# LO.net
KiCad netlist of a schematic drawn in Altium Designer
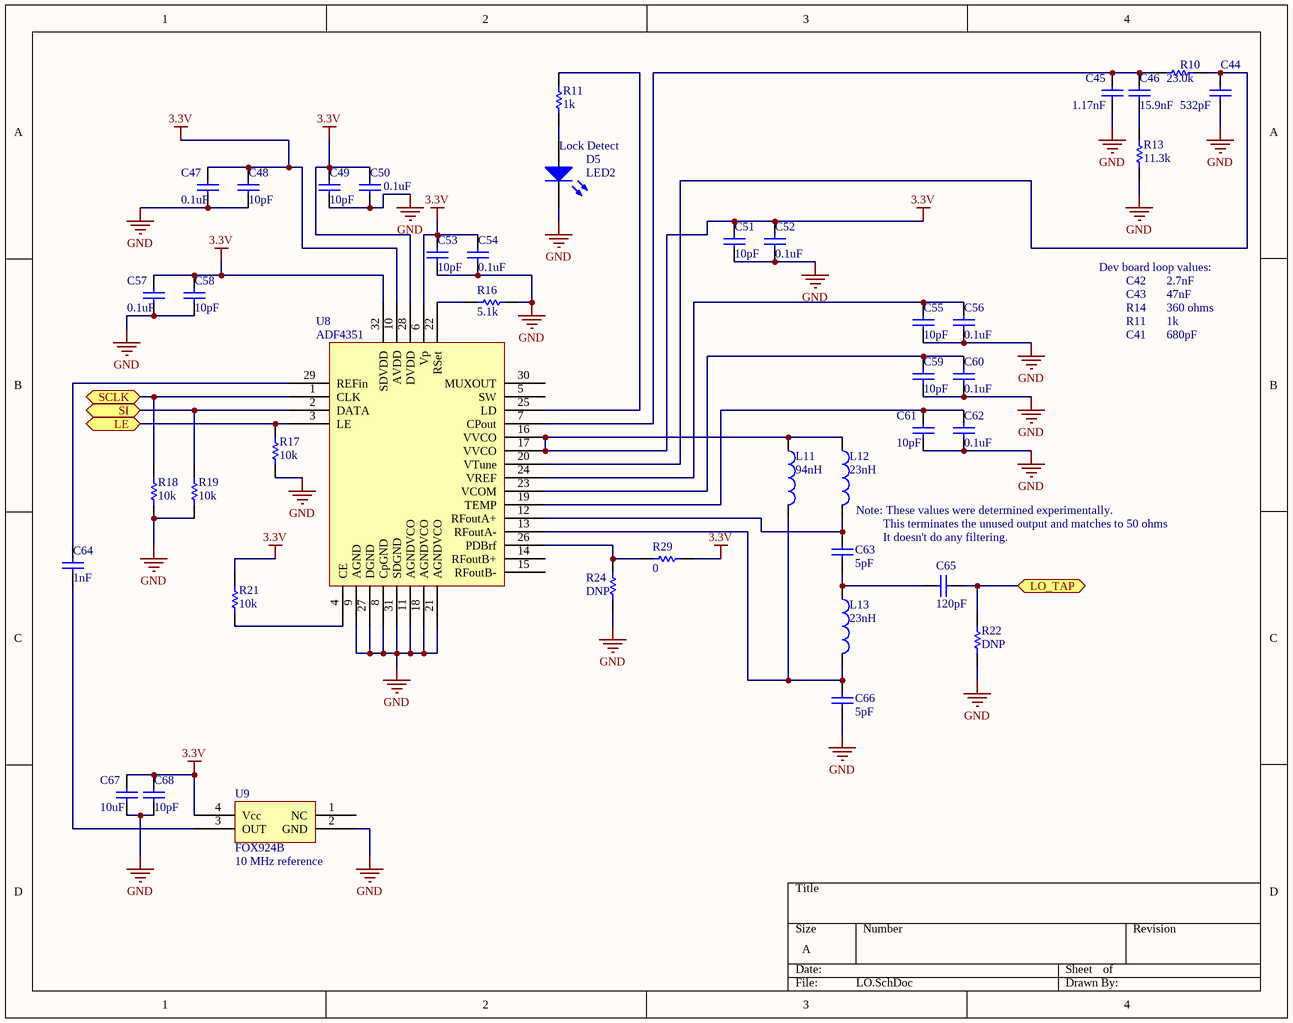
[diagram p0: LO.SchDoc]

(export (version "E")
  (design (tool "Eeschema 10.0.6"))
  (components
    (comp (ref "C44")
      (value "532pF")
      (footprint "0402")
      (description "Capacitor (Semiconductor SIM Model)")
      (fields (field (name "Comment") "Cap Semi") (field (name "PUBLISHER") "Altium Limited"))
      (libsource (lib "Miscellaneous Devices") (part "Cap Semi"))
    )
    (comp (ref "C45")
      (value "1.17nF")
      (footprint "0402")
      (description "Capacitor (Semiconductor SIM Model)")
      (fields (field (name "Comment") "Cap Semi") (field (name "PUBLISHER") "Altium Limited"))
      (libsource (lib "Miscellaneous Devices") (part "Cap Semi"))
    )
    (comp (ref "C46")
      (value "15.9nF")
      (footprint "0402")
      (description "Capacitor (Semiconductor SIM Model)")
      (fields (field (name "Comment") "Cap Semi") (field (name "PUBLISHER") "Altium Limited"))
      (libsource (lib "Miscellaneous Devices") (part "Cap Semi"))
    )
    (comp (ref "C47")
      (value "0.1uF")
      (footprint "0402")
      (description "Capacitor (Semiconductor SIM Model)")
      (fields (field (name "Comment") "Cap Semi") (field (name "PUBLISHER") "Altium Limited"))
      (libsource (lib "Miscellaneous Devices") (part "Cap Semi"))
    )
    (comp (ref "C48")
      (value "10pF")
      (footprint "0402")
      (description "Capacitor (Semiconductor SIM Model)")
      (fields (field (name "Comment") "Cap Semi") (field (name "PUBLISHER") "Altium Limited"))
      (libsource (lib "Miscellaneous Devices") (part "Cap Semi"))
    )
    (comp (ref "C49")
      (value "10pF")
      (footprint "0402")
      (description "Capacitor (Semiconductor SIM Model)")
      (fields (field (name "Comment") "Cap Semi") (field (name "PUBLISHER") "Altium Limited"))
      (libsource (lib "Miscellaneous Devices") (part "Cap Semi"))
    )
    (comp (ref "C50")
      (value "0.1uF")
      (footprint "0402")
      (description "Capacitor (Semiconductor SIM Model)")
      (fields (field (name "Comment") "Cap Semi") (field (name "PUBLISHER") "Altium Limited"))
      (libsource (lib "Miscellaneous Devices") (part "Cap Semi"))
    )
    (comp (ref "C51")
      (value "10pF")
      (footprint "0402")
      (description "Capacitor (Semiconductor SIM Model)")
      (fields (field (name "Comment") "Cap Semi") (field (name "PUBLISHER") "Altium Limited"))
      (libsource (lib "Miscellaneous Devices") (part "Cap Semi"))
    )
    (comp (ref "C52")
      (value "0.1uF")
      (footprint "0402")
      (description "Capacitor (Semiconductor SIM Model)")
      (fields (field (name "Comment") "Cap Semi") (field (name "PUBLISHER") "Altium Limited"))
      (libsource (lib "Miscellaneous Devices") (part "Cap Semi"))
    )
    (comp (ref "C53")
      (value "10pF")
      (footprint "0402")
      (description "Capacitor (Semiconductor SIM Model)")
      (fields (field (name "Comment") "Cap Semi") (field (name "PUBLISHER") "Altium Limited"))
      (libsource (lib "Miscellaneous Devices") (part "Cap Semi"))
    )
    (comp (ref "C54")
      (value "0.1uF")
      (footprint "0402")
      (description "Capacitor (Semiconductor SIM Model)")
      (fields (field (name "Comment") "Cap Semi") (field (name "PUBLISHER") "Altium Limited"))
      (libsource (lib "Miscellaneous Devices") (part "Cap Semi"))
    )
    (comp (ref "C55")
      (value "10pF")
      (footprint "0402")
      (description "Capacitor (Semiconductor SIM Model)")
      (fields (field (name "Comment") "Cap Semi") (field (name "PUBLISHER") "Altium Limited"))
      (libsource (lib "Miscellaneous Devices") (part "Cap Semi"))
    )
    (comp (ref "C56")
      (value "0.1uF")
      (footprint "0402")
      (description "Capacitor (Semiconductor SIM Model)")
      (fields (field (name "Comment") "Cap Semi") (field (name "PUBLISHER") "Altium Limited"))
      (libsource (lib "Miscellaneous Devices") (part "Cap Semi"))
    )
    (comp (ref "C57")
      (value "0.1uF")
      (footprint "0402")
      (description "Capacitor (Semiconductor SIM Model)")
      (fields (field (name "Comment") "Cap Semi") (field (name "PUBLISHER") "Altium Limited"))
      (libsource (lib "Miscellaneous Devices") (part "Cap Semi"))
    )
    (comp (ref "C58")
      (value "10pF")
      (footprint "0402")
      (description "Capacitor (Semiconductor SIM Model)")
      (fields (field (name "Comment") "Cap Semi") (field (name "PUBLISHER") "Altium Limited"))
      (libsource (lib "Miscellaneous Devices") (part "Cap Semi"))
    )
    (comp (ref "C59")
      (value "10pF")
      (footprint "0402")
      (description "Capacitor (Semiconductor SIM Model)")
      (fields (field (name "Comment") "Cap Semi") (field (name "PUBLISHER") "Altium Limited"))
      (libsource (lib "Miscellaneous Devices") (part "Cap Semi"))
    )
    (comp (ref "C60")
      (value "0.1uF")
      (footprint "0402")
      (description "Capacitor (Semiconductor SIM Model)")
      (fields (field (name "Comment") "Cap Semi") (field (name "PUBLISHER") "Altium Limited"))
      (libsource (lib "Miscellaneous Devices") (part "Cap Semi"))
    )
    (comp (ref "C61")
      (value "10pF")
      (footprint "0402")
      (description "Capacitor (Semiconductor SIM Model)")
      (fields (field (name "Comment") "Cap Semi") (field (name "PUBLISHER") "Altium Limited"))
      (libsource (lib "Miscellaneous Devices") (part "Cap Semi"))
    )
    (comp (ref "C62")
      (value "0.1uF")
      (footprint "0402")
      (description "Capacitor (Semiconductor SIM Model)")
      (fields (field (name "Comment") "Cap Semi") (field (name "PUBLISHER") "Altium Limited"))
      (libsource (lib "Miscellaneous Devices") (part "Cap Semi"))
    )
    (comp (ref "C63")
      (value "5pF")
      (footprint "0402")
      (description "Capacitor (Semiconductor SIM Model)")
      (fields (field (name "Comment") "Cap Semi") (field (name "PUBLISHER") "Altium Limited"))
      (libsource (lib "Miscellaneous Devices") (part "Cap Semi"))
    )
    (comp (ref "C64")
      (value "1nF")
      (footprint "0402")
      (description "Capacitor (Semiconductor SIM Model)")
      (fields (field (name "Comment") "Cap Semi") (field (name "PUBLISHER") "Altium Limited"))
      (libsource (lib "Miscellaneous Devices") (part "Cap Semi"))
    )
    (comp (ref "C65")
      (value "120pF")
      (footprint "0402")
      (description "Capacitor (Semiconductor SIM Model)")
      (fields (field (name "Comment") "Cap Semi") (field (name "PUBLISHER") "Altium Limited"))
      (libsource (lib "Miscellaneous Devices") (part "Cap Semi"))
    )
    (comp (ref "C66")
      (value "5pF")
      (footprint "0402")
      (description "Capacitor (Semiconductor SIM Model)")
      (fields (field (name "Comment") "Cap Semi") (field (name "PUBLISHER") "Altium Limited"))
      (libsource (lib "Miscellaneous Devices") (part "Cap Semi"))
    )
    (comp (ref "C67")
      (value "10uF")
      (footprint "0402")
      (description "Capacitor (Semiconductor SIM Model)")
      (fields (field (name "Comment") "Cap Semi") (field (name "PUBLISHER") "Altium Limited"))
      (libsource (lib "Miscellaneous Devices") (part "Cap Semi"))
    )
    (comp (ref "C68")
      (value "10pF")
      (footprint "0402")
      (description "Capacitor (Semiconductor SIM Model)")
      (fields (field (name "Comment") "Cap Semi") (field (name "PUBLISHER") "Altium Limited"))
      (libsource (lib "Miscellaneous Devices") (part "Cap Semi"))
    )
    (comp (ref "D5")
      (value "LED2")
      (footprint "0603")
      (description "Typical RED, GREEN, YELLOW, AMBER GaAs LED")
      (fields (field (name "PUBLISHER") "Altium Limited"))
      (libsource (lib "Miscellaneous Devices") (part "LED2"))
    )
    (comp (ref "L11")
      (value "94nH")
      (footprint "0402")
      (description "Inductor")
      (fields (field (name "PUBLISHER") "Altium Limited"))
      (libsource (lib "Miscellaneous Devices") (part "Inductor"))
    )
    (comp (ref "L12")
      (value "23nH")
      (footprint "0402")
      (description "Inductor")
      (fields (field (name "PUBLISHER") "Altium Limited"))
      (libsource (lib "Miscellaneous Devices") (part "Inductor"))
    )
    (comp (ref "L13")
      (value "23nH")
      (footprint "0402")
      (description "Inductor")
      (fields (field (name "PUBLISHER") "Altium Limited"))
      (libsource (lib "Miscellaneous Devices") (part "Inductor"))
    )
    (comp (ref "R10")
      (value "23.0k")
      (footprint "0402")
      (description "Semiconductor Resistor")
      (fields (field (name "Comment") "Res Semi") (field (name "PUBLISHER") "Altium Limited"))
      (libsource (lib "Miscellaneous Devices") (part "Res Semi"))
    )
    (comp (ref "R11")
      (value "1k")
      (footprint "0402")
      (description "Semiconductor Resistor")
      (fields (field (name "Comment") "Res Semi") (field (name "PUBLISHER") "Altium Limited"))
      (libsource (lib "Miscellaneous Devices") (part "Res Semi"))
    )
    (comp (ref "R13")
      (value "11.3k")
      (footprint "0402")
      (description "Semiconductor Resistor")
      (fields (field (name "Comment") "Res Semi") (field (name "PUBLISHER") "Altium Limited"))
      (libsource (lib "Miscellaneous Devices") (part "Res Semi"))
    )
    (comp (ref "R16")
      (value "5.1k")
      (footprint "0402")
      (description "Semiconductor Resistor")
      (fields (field (name "Comment") "Res Semi") (field (name "PUBLISHER") "Altium Limited"))
      (libsource (lib "Miscellaneous Devices") (part "Res Semi"))
    )
    (comp (ref "R17")
      (value "10k")
      (footprint "0402")
      (description "Semiconductor Resistor")
      (fields (field (name "Comment") "Res Semi") (field (name "PUBLISHER") "Altium Limited"))
      (libsource (lib "Miscellaneous Devices") (part "Res Semi"))
    )
    (comp (ref "R18")
      (value "10k")
      (footprint "0402")
      (description "Semiconductor Resistor")
      (fields (field (name "Comment") "Res Semi") (field (name "PUBLISHER") "Altium Limited"))
      (libsource (lib "Miscellaneous Devices") (part "Res Semi"))
    )
    (comp (ref "R19")
      (value "10k")
      (footprint "0402")
      (description "Semiconductor Resistor")
      (fields (field (name "Comment") "Res Semi") (field (name "PUBLISHER") "Altium Limited"))
      (libsource (lib "Miscellaneous Devices") (part "Res Semi"))
    )
    (comp (ref "R21")
      (value "10k")
      (footprint "0402")
      (description "Semiconductor Resistor")
      (fields (field (name "Comment") "Res Semi") (field (name "PUBLISHER") "Altium Limited"))
      (libsource (lib "Miscellaneous Devices") (part "Res Semi"))
    )
    (comp (ref "R22")
      (value "DNP")
      (footprint "0402")
      (description "Semiconductor Resistor")
      (fields (field (name "Comment") "Res Semi") (field (name "PUBLISHER") "Altium Limited"))
      (libsource (lib "Miscellaneous Devices") (part "Res Semi"))
    )
    (comp (ref "R24")
      (value "DNP")
      (footprint "0402")
      (description "Semiconductor Resistor")
      (fields (field (name "Comment") "Res Semi") (field (name "PUBLISHER") "Altium Limited"))
      (libsource (lib "Miscellaneous Devices") (part "Res Semi"))
    )
    (comp (ref "R29")
      (value "0")
      (footprint "0402")
      (description "Semiconductor Resistor")
      (fields (field (name "Comment") "Res Semi") (field (name "PUBLISHER") "Altium Limited"))
      (libsource (lib "Miscellaneous Devices") (part "Res Semi"))
    )
    (comp (ref "U8")
      (value "ADF4351")
      (footprint "QFN50P500X500-32VBN")
      (description "VCO")
      (libsource (lib "shield_components") (part "ADF4350"))
    )
    (comp (ref "U9")
      (value "FOX924B")
      (footprint "FOX924")
      (libsource (lib "shield_components") (part "FOX924"))
    )
  )
  (nets
    (net (code "1") (name "/LE") (class "Default")
      (node (ref "R17") (pin "1") (pinfunction "1_1") (pintype "passive"))
      (node (ref "U8") (pin "3") (pinfunction "LE_3") (pintype "passive"))
    )
    (net (code "2") (name "/LO_TAP") (class "Default")
      (node (ref "C65") (pin "2") (pinfunction "2_2") (pintype "passive"))
      (node (ref "R22") (pin "1") (pinfunction "1_1") (pintype "passive"))
    )
    (net (code "3") (name "/SCLK") (class "Default")
      (node (ref "R18") (pin "1") (pinfunction "1_1") (pintype "passive"))
      (node (ref "U8") (pin "1") (pinfunction "CLK_1") (pintype "passive"))
    )
    (net (code "4") (name "/SI") (class "Default")
      (node (ref "R19") (pin "1") (pinfunction "1_1") (pintype "passive"))
      (node (ref "U8") (pin "2") (pinfunction "DATA_2") (pintype "passive"))
    )
    (net (code "5") (name "3.3V") (class "Default")
      (node (ref "C47") (pin "1") (pinfunction "1_1") (pintype "passive"))
      (node (ref "C48") (pin "1") (pinfunction "1_1") (pintype "passive"))
      (node (ref "C49") (pin "1") (pinfunction "1_1") (pintype "passive"))
      (node (ref "C50") (pin "1") (pinfunction "1_1") (pintype "passive"))
      (node (ref "C51") (pin "1") (pinfunction "1_1") (pintype "passive"))
      (node (ref "C52") (pin "1") (pinfunction "1_1") (pintype "passive"))
      (node (ref "C53") (pin "1") (pinfunction "1_1") (pintype "passive"))
      (node (ref "C54") (pin "1") (pinfunction "1_1") (pintype "passive"))
      (node (ref "C57") (pin "1") (pinfunction "1_1") (pintype "passive"))
      (node (ref "C58") (pin "1") (pinfunction "1_1") (pintype "passive"))
      (node (ref "C67") (pin "1") (pinfunction "1_1") (pintype "passive"))
      (node (ref "C68") (pin "1") (pinfunction "1_1") (pintype "passive"))
      (node (ref "L11") (pin "1") (pinfunction "1_1") (pintype "passive"))
      (node (ref "L12") (pin "1") (pinfunction "1_1") (pintype "passive"))
      (node (ref "R21") (pin "1") (pinfunction "1_1") (pintype "passive"))
      (node (ref "R29") (pin "2") (pinfunction "2_2") (pintype "passive"))
      (node (ref "U8") (pin "10") (pinfunction "AVDD_10") (pintype "power_in"))
      (node (ref "U8") (pin "16") (pinfunction "VVCO_16") (pintype "power_in"))
      (node (ref "U8") (pin "17") (pinfunction "VVCO_17") (pintype "power_in"))
      (node (ref "U8") (pin "28") (pinfunction "DVDD_28") (pintype "power_in"))
      (node (ref "U8") (pin "32") (pinfunction "SDVDD_32") (pintype "power_in"))
      (node (ref "U8") (pin "6") (pinfunction "Vp_6") (pintype "power_in"))
      (node (ref "U9") (pin "4") (pinfunction "Vcc_4") (pintype "passive"))
    )
    (net (code "6") (name "GND") (class "Default")
      (node (ref "C44") (pin "2") (pinfunction "2_2") (pintype "passive"))
      (node (ref "C45") (pin "2") (pinfunction "2_2") (pintype "passive"))
      (node (ref "C47") (pin "2") (pinfunction "2_2") (pintype "passive"))
      (node (ref "C48") (pin "2") (pinfunction "2_2") (pintype "passive"))
      (node (ref "C49") (pin "2") (pinfunction "2_2") (pintype "passive"))
      (node (ref "C50") (pin "2") (pinfunction "2_2") (pintype "passive"))
      (node (ref "C51") (pin "2") (pinfunction "2_2") (pintype "passive"))
      (node (ref "C52") (pin "2") (pinfunction "2_2") (pintype "passive"))
      (node (ref "C53") (pin "2") (pinfunction "2_2") (pintype "passive"))
      (node (ref "C54") (pin "2") (pinfunction "2_2") (pintype "passive"))
      (node (ref "C55") (pin "2") (pinfunction "2_2") (pintype "passive"))
      (node (ref "C56") (pin "2") (pinfunction "2_2") (pintype "passive"))
      (node (ref "C57") (pin "2") (pinfunction "2_2") (pintype "passive"))
      (node (ref "C58") (pin "2") (pinfunction "2_2") (pintype "passive"))
      (node (ref "C59") (pin "2") (pinfunction "2_2") (pintype "passive"))
      (node (ref "C60") (pin "2") (pinfunction "2_2") (pintype "passive"))
      (node (ref "C61") (pin "2") (pinfunction "2_2") (pintype "passive"))
      (node (ref "C62") (pin "2") (pinfunction "2_2") (pintype "passive"))
      (node (ref "C66") (pin "2") (pinfunction "2_2") (pintype "passive"))
      (node (ref "C67") (pin "2") (pinfunction "2_2") (pintype "passive"))
      (node (ref "C68") (pin "2") (pinfunction "2_2") (pintype "passive"))
      (node (ref "D5") (pin "2") (pinfunction "K_2") (pintype "passive"))
      (node (ref "R13") (pin "2") (pinfunction "2_2") (pintype "passive"))
      (node (ref "R16") (pin "1") (pinfunction "1_1") (pintype "passive"))
      (node (ref "R17") (pin "2") (pinfunction "2_2") (pintype "passive"))
      (node (ref "R18") (pin "2") (pinfunction "2_2") (pintype "passive"))
      (node (ref "R19") (pin "2") (pinfunction "2_2") (pintype "passive"))
      (node (ref "R22") (pin "2") (pinfunction "2_2") (pintype "passive"))
      (node (ref "R24") (pin "2") (pinfunction "2_2") (pintype "passive"))
      (node (ref "U8") (pin "11") (pinfunction "AGNDVCO_11") (pintype "power_in"))
      (node (ref "U8") (pin "18") (pinfunction "AGNDVCO_18") (pintype "power_in"))
      (node (ref "U8") (pin "21") (pinfunction "AGNDVCO_21") (pintype "power_in"))
      (node (ref "U8") (pin "27") (pinfunction "DGND_27") (pintype "power_in"))
      (node (ref "U8") (pin "31") (pinfunction "SDGND_31") (pintype "power_in"))
      (node (ref "U8") (pin "8") (pinfunction "CpGND_8") (pintype "power_in"))
      (node (ref "U8") (pin "9") (pinfunction "AGND_9") (pintype "power_in"))
      (node (ref "U9") (pin "2") (pinfunction "GND_2") (pintype "passive"))
    )
    (net (code "7") (name "Net-(C46-Pad2)") (class "Default")
      (node (ref "C46") (pin "2") (pinfunction "2_2") (pintype "passive"))
      (node (ref "R13") (pin "1") (pinfunction "1_1") (pintype "passive"))
    )
    (net (code "8") (name "Net-(C63-Pad2)") (class "Default")
      (node (ref "C63") (pin "2") (pinfunction "2_2") (pintype "passive"))
      (node (ref "C65") (pin "1") (pinfunction "1_1") (pintype "passive"))
      (node (ref "L13") (pin "1") (pinfunction "1_1") (pintype "passive"))
    )
    (net (code "9") (name "Net-(D5-A)") (class "Default")
      (node (ref "D5") (pin "1") (pinfunction "A_1") (pintype "passive"))
      (node (ref "R11") (pin "2") (pinfunction "2_2") (pintype "passive"))
    )
    (net (code "10") (name "Net-(U8-CE)") (class "Default")
      (node (ref "R21") (pin "2") (pinfunction "2_2") (pintype "passive"))
      (node (ref "U8") (pin "4") (pinfunction "CE_4") (pintype "passive"))
    )
    (net (code "11") (name "Net-(U8-CPout)") (class "Default")
      (node (ref "C45") (pin "1") (pinfunction "1_1") (pintype "passive"))
      (node (ref "C46") (pin "1") (pinfunction "1_1") (pintype "passive"))
      (node (ref "R10") (pin "2") (pinfunction "2_2") (pintype "passive"))
      (node (ref "U8") (pin "7") (pinfunction "CPout_7") (pintype "passive"))
    )
    (net (code "12") (name "Net-(U8-LD)") (class "Default")
      (node (ref "R11") (pin "1") (pinfunction "1_1") (pintype "passive"))
      (node (ref "U8") (pin "25") (pinfunction "LD_25") (pintype "passive"))
    )
    (net (code "13") (name "Net-(U8-PDBrf)") (class "Default")
      (node (ref "R24") (pin "1") (pinfunction "1_1") (pintype "passive"))
      (node (ref "R29") (pin "1") (pinfunction "1_1") (pintype "passive"))
      (node (ref "U8") (pin "26") (pinfunction "PDBrf_26") (pintype "passive"))
    )
    (net (code "14") (name "Net-(U8-REFin)") (class "Default")
      (node (ref "C64") (pin "1") (pinfunction "1_1") (pintype "passive"))
      (node (ref "U8") (pin "29") (pinfunction "REFin_29") (pintype "passive"))
    )
    (net (code "15") (name "Net-(U8-RFoutA+)") (class "Default")
      (node (ref "C63") (pin "1") (pinfunction "1_1") (pintype "passive"))
      (node (ref "L12") (pin "2") (pinfunction "2_2") (pintype "passive"))
      (node (ref "U8") (pin "12") (pinfunction "RFoutA+_12") (pintype "passive"))
    )
    (net (code "16") (name "Net-(U8-RFoutA-)") (class "Default")
      (node (ref "C66") (pin "1") (pinfunction "1_1") (pintype "passive"))
      (node (ref "L11") (pin "2") (pinfunction "2_2") (pintype "passive"))
      (node (ref "L13") (pin "2") (pinfunction "2_2") (pintype "passive"))
      (node (ref "U8") (pin "13") (pinfunction "RFoutA-_13") (pintype "passive"))
    )
    (net (code "17") (name "Net-(U8-RSet)") (class "Default")
      (node (ref "R16") (pin "2") (pinfunction "2_2") (pintype "passive"))
      (node (ref "U8") (pin "22") (pinfunction "RSet_22") (pintype "passive"))
    )
    (net (code "18") (name "Net-(U8-TEMP)") (class "Default")
      (node (ref "C61") (pin "1") (pinfunction "1_1") (pintype "passive"))
      (node (ref "C62") (pin "1") (pinfunction "1_1") (pintype "passive"))
      (node (ref "U8") (pin "19") (pinfunction "TEMP_19") (pintype "passive"))
    )
    (net (code "19") (name "Net-(U8-VCOM)") (class "Default")
      (node (ref "C59") (pin "1") (pinfunction "1_1") (pintype "passive"))
      (node (ref "C60") (pin "1") (pinfunction "1_1") (pintype "passive"))
      (node (ref "U8") (pin "23") (pinfunction "VCOM_23") (pintype "power_in"))
    )
    (net (code "20") (name "Net-(U8-VREF)") (class "Default")
      (node (ref "C55") (pin "1") (pinfunction "1_1") (pintype "passive"))
      (node (ref "C56") (pin "1") (pinfunction "1_1") (pintype "passive"))
      (node (ref "U8") (pin "24") (pinfunction "VREF_24") (pintype "power_in"))
    )
    (net (code "21") (name "Net-(U8-VTune)") (class "Default")
      (node (ref "C44") (pin "1") (pinfunction "1_1") (pintype "passive"))
      (node (ref "R10") (pin "1") (pinfunction "1_1") (pintype "passive"))
      (node (ref "U8") (pin "20") (pinfunction "VTune_20") (pintype "passive"))
    )
    (net (code "22") (name "Net-(U9-OUT)") (class "Default")
      (node (ref "C64") (pin "2") (pinfunction "2_2") (pintype "passive"))
      (node (ref "U9") (pin "3") (pinfunction "OUT_3") (pintype "passive"))
    )
    (net (code "23") (name "unconnected-(U8-MUXOUT-Pad30)") (class "Default")
      (node (ref "U8") (pin "30") (pinfunction "MUXOUT_30") (pintype "passive"))
    )
    (net (code "24") (name "unconnected-(U8-RFoutB+-Pad14)") (class "Default")
      (node (ref "U8") (pin "14") (pinfunction "RFoutB+_14") (pintype "passive"))
    )
    (net (code "25") (name "unconnected-(U8-RFoutB--Pad15)") (class "Default")
      (node (ref "U8") (pin "15") (pinfunction "RFoutB-_15") (pintype "passive"))
    )
    (net (code "26") (name "unconnected-(U8-SW-Pad5)") (class "Default")
      (node (ref "U8") (pin "5") (pinfunction "SW_5") (pintype "passive"))
    )
    (net (code "27") (name "unconnected-(U9-NC-Pad1)") (class "Default")
      (node (ref "U9") (pin "1") (pinfunction "NC_1") (pintype "passive"))
    )
  )
)
